# Low_Noise_PS_Bottom_SMD.net
KiCad netlist of a schematic drawn in EAGLE
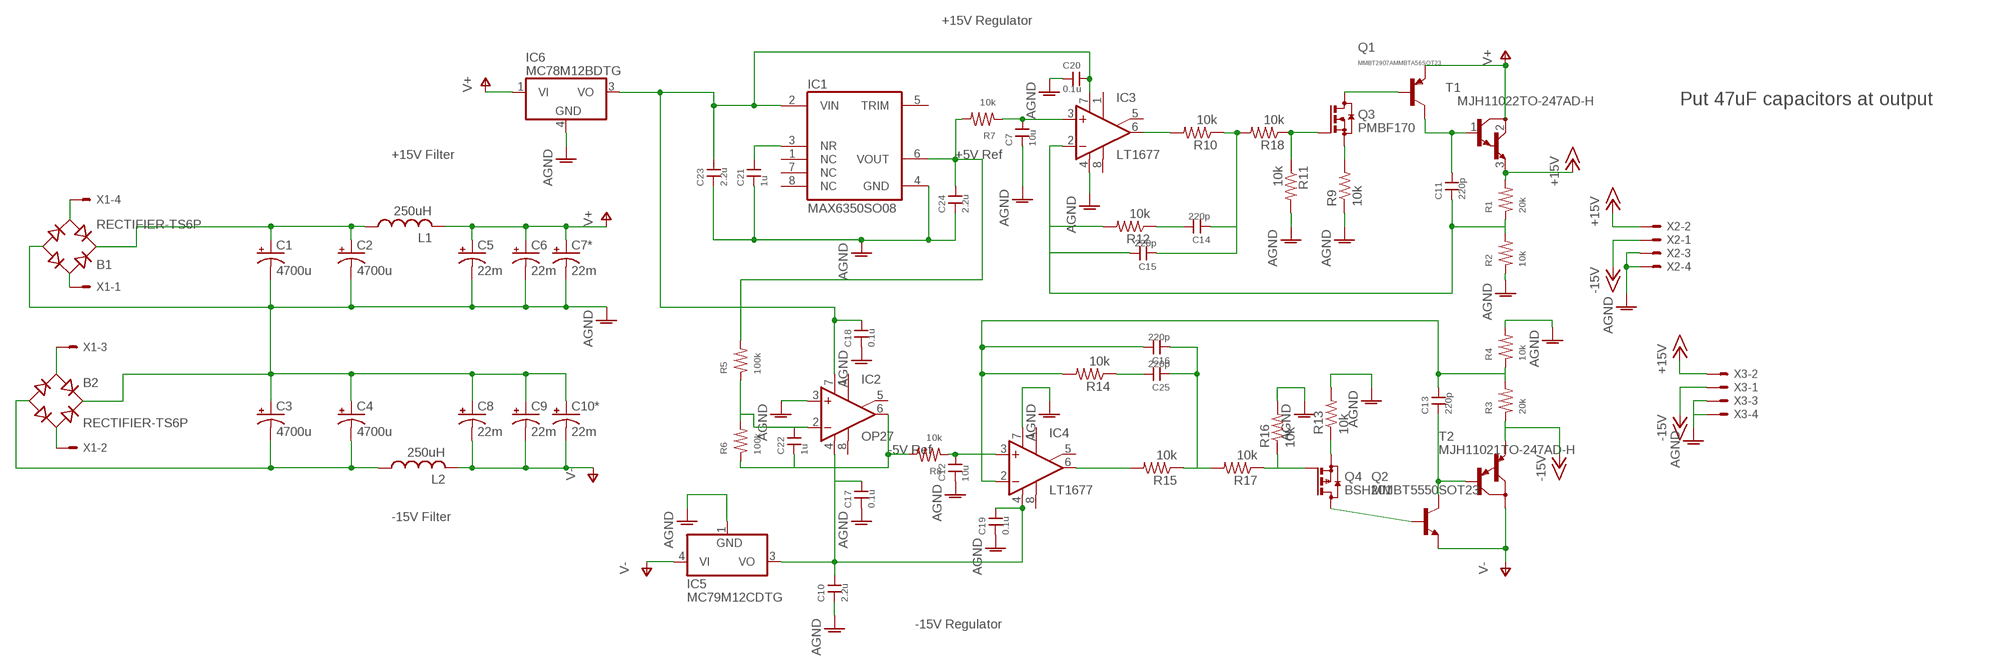
[diagram p0: schematic, sheet 1]

(export (version "E")
  (design (tool "Eeschema 10.0.6"))
  (components
    (comp (ref "B1")
      (value "RECTIFIER-TS6P")
      (footprint "eagle-import:TS6P")
      (libsource (lib "eagle-import") (part "RECTIFIER-TS6P"))
    )
    (comp (ref "B2")
      (value "RECTIFIER-TS6P")
      (footprint "eagle-import:TS6P")
      (libsource (lib "eagle-import") (part "RECTIFIER-TS6P"))
    )
    (comp (ref "C1")
      (value "4700u")
      (footprint "eagle-import:E7,5-18")
      (libsource (lib "eagle-import") (part "CPOL-USE7.5-18"))
    )
    (comp (ref "C2")
      (value "4700u")
      (footprint "eagle-import:E7,5-18")
      (libsource (lib "eagle-import") (part "CPOL-USE7.5-18"))
    )
    (comp (ref "C3")
      (value "4700u")
      (footprint "eagle-import:E7,5-18")
      (libsource (lib "eagle-import") (part "CPOL-USE7.5-18"))
    )
    (comp (ref "C4")
      (value "4700u")
      (footprint "eagle-import:E7,5-18")
      (libsource (lib "eagle-import") (part "CPOL-USE7.5-18"))
    )
    (comp (ref "C5")
      (value "22m")
      (footprint "eagle-import:EB35D")
      (libsource (lib "eagle-import") (part "CPOL-USEB35D"))
    )
    (comp (ref "C6")
      (value "22m")
      (footprint "eagle-import:EB35D")
      (libsource (lib "eagle-import") (part "CPOL-USEB35D"))
    )
    (comp (ref "C7")
      (value "10u")
      (footprint "eagle-import:1206")
      (libsource (lib "eagle-import") (part "CAP1206"))
    )
    (comp (ref "C7*")
      (value "22m")
      (footprint "eagle-import:EB35D")
      (libsource (lib "eagle-import") (part "CPOL-USEB35D"))
    )
    (comp (ref "C8")
      (value "22m")
      (footprint "eagle-import:EB35D")
      (libsource (lib "eagle-import") (part "CPOL-USEB35D"))
    )
    (comp (ref "C9")
      (value "22m")
      (footprint "eagle-import:EB35D")
      (libsource (lib "eagle-import") (part "CPOL-USEB35D"))
    )
    (comp (ref "C10")
      (value "2.2u")
      (footprint "eagle-import:1206")
      (libsource (lib "eagle-import") (part "CAP1206"))
    )
    (comp (ref "C10*")
      (value "22m")
      (footprint "eagle-import:EB35D")
      (libsource (lib "eagle-import") (part "CPOL-USEB35D"))
    )
    (comp (ref "C11")
      (value "220p")
      (footprint "eagle-import:1206")
      (libsource (lib "eagle-import") (part "CAP1206"))
    )
    (comp (ref "C12")
      (value "10u")
      (footprint "eagle-import:1206")
      (libsource (lib "eagle-import") (part "CAP1206"))
    )
    (comp (ref "C13")
      (value "220p")
      (footprint "eagle-import:1206")
      (libsource (lib "eagle-import") (part "CAP1206"))
    )
    (comp (ref "C14")
      (value "220p")
      (footprint "eagle-import:1206")
      (libsource (lib "eagle-import") (part "CAP1206"))
    )
    (comp (ref "C15")
      (value "220p")
      (footprint "eagle-import:1206")
      (libsource (lib "eagle-import") (part "CAP1206"))
    )
    (comp (ref "C16")
      (value "220p")
      (footprint "eagle-import:1206")
      (libsource (lib "eagle-import") (part "CAP1206"))
    )
    (comp (ref "C17")
      (value "0.1u")
      (footprint "eagle-import:1206")
      (libsource (lib "eagle-import") (part "CAP1206"))
    )
    (comp (ref "C18")
      (value "0.1u")
      (footprint "eagle-import:1206")
      (libsource (lib "eagle-import") (part "CAP1206"))
    )
    (comp (ref "C19")
      (value "0.1u")
      (footprint "eagle-import:1206")
      (libsource (lib "eagle-import") (part "CAP1206"))
    )
    (comp (ref "C20")
      (value "0.1u")
      (footprint "eagle-import:1206")
      (libsource (lib "eagle-import") (part "CAP1206"))
    )
    (comp (ref "C21")
      (value "1u")
      (footprint "eagle-import:1206")
      (libsource (lib "eagle-import") (part "CAP1206"))
    )
    (comp (ref "C22")
      (value "1u")
      (footprint "eagle-import:1206")
      (libsource (lib "eagle-import") (part "CAP1206"))
    )
    (comp (ref "C23")
      (value "2.2u")
      (footprint "eagle-import:1206")
      (libsource (lib "eagle-import") (part "CAP1206"))
    )
    (comp (ref "C24")
      (value "2.2u")
      (footprint "eagle-import:1206")
      (libsource (lib "eagle-import") (part "CAP1206"))
    )
    (comp (ref "C25")
      (value "220p")
      (footprint "eagle-import:1206")
      (libsource (lib "eagle-import") (part "CAP1206"))
    )
    (comp (ref "IC1")
      (value "MAX6350SO08")
      (footprint "eagle-import:SO08")
      (libsource (lib "eagle-import") (part "MAX6350SO08"))
    )
    (comp (ref "IC2")
      (value "OP27")
      (footprint "eagle-import:SO08")
      (libsource (lib "eagle-import") (part "OPAMP-SO"))
    )
    (comp (ref "IC3")
      (value "LT1677")
      (footprint "eagle-import:SO08")
      (libsource (lib "eagle-import") (part "OPAMP-SO"))
    )
    (comp (ref "IC4")
      (value "LT1677")
      (footprint "eagle-import:SO08")
      (libsource (lib "eagle-import") (part "OPAMP-SO"))
    )
    (comp (ref "IC5")
      (value "MC79M12CDTG")
      (footprint "eagle-import:DPACK_3")
      (libsource (lib "eagle-import") (part "MC79M12CDTG"))
    )
    (comp (ref "IC6")
      (value "MC78M12BDTG")
      (footprint "eagle-import:DPACK_3")
      (libsource (lib "eagle-import") (part "MC78M12BDTG"))
    )
    (comp (ref "L1")
      (value "250uH")
      (footprint "eagle-import:5721-RC")
      (libsource (lib "eagle-import") (part "INDUCTOR5721-RC"))
    )
    (comp (ref "L2")
      (value "250uH")
      (footprint "eagle-import:5721-RC")
      (libsource (lib "eagle-import") (part "INDUCTOR5721-RC"))
    )
    (comp (ref "Q1")
      (value "MMBT2907AMMBTA56SOT23")
      (footprint "eagle-import:SOT23")
      (libsource (lib "eagle-import") (part "MMBT2907ASOT23MMBTA56"))
    )
    (comp (ref "Q2")
      (value "MMBT5550SOT23")
      (footprint "eagle-import:SOT23")
      (libsource (lib "eagle-import") (part "MMBT5550SOT23"))
    )
    (comp (ref "Q3")
      (value "PMBF170")
      (footprint "eagle-import:SOT23")
      (libsource (lib "eagle-import") (part "PMBF170"))
    )
    (comp (ref "Q4")
      (value "BSH201")
      (footprint "eagle-import:SOT23")
      (libsource (lib "eagle-import") (part "BSH201"))
    )
    (comp (ref "R1")
      (value "20k")
      (footprint "eagle-import:1206")
      (libsource (lib "eagle-import") (part "RES1206"))
    )
    (comp (ref "R2")
      (value "10k")
      (footprint "eagle-import:1206")
      (libsource (lib "eagle-import") (part "RES1206"))
    )
    (comp (ref "R3")
      (value "20k")
      (footprint "eagle-import:1206")
      (libsource (lib "eagle-import") (part "RES1206"))
    )
    (comp (ref "R4")
      (value "10k")
      (footprint "eagle-import:1206")
      (libsource (lib "eagle-import") (part "RES1206"))
    )
    (comp (ref "R5")
      (value "100k")
      (footprint "eagle-import:1206")
      (libsource (lib "eagle-import") (part "RES1206"))
    )
    (comp (ref "R6")
      (value "100k")
      (footprint "eagle-import:1206")
      (libsource (lib "eagle-import") (part "RES1206"))
    )
    (comp (ref "R7")
      (value "10k")
      (footprint "eagle-import:1206")
      (libsource (lib "eagle-import") (part "RES1206"))
    )
    (comp (ref "R8")
      (value "10k")
      (footprint "eagle-import:1206")
      (libsource (lib "eagle-import") (part "RES1206"))
    )
    (comp (ref "R9")
      (value "10k")
      (footprint "eagle-import:R1206")
      (libsource (lib "eagle-import") (part "R-US_R1206"))
    )
    (comp (ref "R10")
      (value "10k")
      (footprint "eagle-import:R1206")
      (libsource (lib "eagle-import") (part "R-US_R1206"))
    )
    (comp (ref "R11")
      (value "10k")
      (footprint "eagle-import:R1206")
      (libsource (lib "eagle-import") (part "R-US_R1206"))
    )
    (comp (ref "R12")
      (value "10k")
      (footprint "eagle-import:R1206")
      (libsource (lib "eagle-import") (part "R-US_R1206"))
    )
    (comp (ref "R13")
      (value "10k")
      (footprint "eagle-import:R1206")
      (libsource (lib "eagle-import") (part "R-US_R1206"))
    )
    (comp (ref "R14")
      (value "10k")
      (footprint "eagle-import:R1206")
      (libsource (lib "eagle-import") (part "R-US_R1206"))
    )
    (comp (ref "R15")
      (value "10k")
      (footprint "eagle-import:R1206")
      (libsource (lib "eagle-import") (part "R-US_R1206"))
    )
    (comp (ref "R16")
      (value "10k")
      (footprint "eagle-import:R1206")
      (libsource (lib "eagle-import") (part "R-US_R1206"))
    )
    (comp (ref "R17")
      (value "10k")
      (footprint "eagle-import:R1206")
      (libsource (lib "eagle-import") (part "R-US_R1206"))
    )
    (comp (ref "R18")
      (value "10k")
      (footprint "eagle-import:R1206")
      (libsource (lib "eagle-import") (part "R-US_R1206"))
    )
    (comp (ref "T1")
      (value "MJH11022TO-247AD-H")
      (footprint "eagle-import:TO-247AD-H")
      (libsource (lib "eagle-import") (part "MJH11022TO-247AD-H"))
    )
    (comp (ref "T2")
      (value "MJH11021TO-247AD-H")
      (footprint "eagle-import:TO-247AD-H")
      (libsource (lib "eagle-import") (part "MJH11021TO-247AD-H"))
    )
    (comp (ref "X1")
      (value "5566-4RA")
      (footprint "eagle-import:5566-4-RA")
      (libsource (lib "eagle-import") (part "5566-4RA"))
    )
    (comp (ref "X2")
      (value "5566-4RA")
      (footprint "eagle-import:5566-4-RA")
      (libsource (lib "eagle-import") (part "5566-4RA"))
    )
    (comp (ref "X3")
      (value "5566-4RA")
      (footprint "eagle-import:5566-4-RA")
      (libsource (lib "eagle-import") (part "5566-4RA"))
    )
  )
  (nets
    (net (code "1") (name "+15V") (class "Default")
      (node (ref "R1") (pin "2") (pinfunction "P$2_2") (pintype "passive"))
      (node (ref "T1") (pin "3") (pinfunction "E_3") (pintype "passive"))
      (node (ref "X2") (pin "2") (pinfunction "S_2") (pintype "passive"))
      (node (ref "X3") (pin "2") (pinfunction "S_2") (pintype "passive"))
    )
    (net (code "2") (name "-15V") (class "Default")
      (node (ref "R3") (pin "1") (pinfunction "P$1_1") (pintype "passive"))
      (node (ref "T2") (pin "3") (pinfunction "E_3") (pintype "passive"))
      (node (ref "X2") (pin "1") (pinfunction "S_1") (pintype "passive"))
      (node (ref "X3") (pin "1") (pinfunction "S_1") (pintype "passive"))
    )
    (net (code "3") (name "AGND") (class "Default")
      (node (ref "B1") (pin "-") (pinfunction "-_-") (pintype "passive"))
      (node (ref "B2") (pin "+") (pinfunction "+_+") (pintype "passive"))
      (node (ref "C1") (pin "-") (pinfunction "-_-") (pintype "passive"))
      (node (ref "C10") (pin "1") (pinfunction "P$1_1") (pintype "passive"))
      (node (ref "C10*") (pin "+") (pinfunction "+_+") (pintype "passive"))
      (node (ref "C12") (pin "1") (pinfunction "P$1_1") (pintype "passive"))
      (node (ref "C17") (pin "1") (pinfunction "P$1_1") (pintype "passive"))
      (node (ref "C18") (pin "1") (pinfunction "P$1_1") (pintype "passive"))
      (node (ref "C19") (pin "1") (pinfunction "P$1_1") (pintype "passive"))
      (node (ref "C2") (pin "-") (pinfunction "-_-") (pintype "passive"))
      (node (ref "C20") (pin "1") (pinfunction "P$1_1") (pintype "passive"))
      (node (ref "C21") (pin "1") (pinfunction "P$1_1") (pintype "passive"))
      (node (ref "C23") (pin "1") (pinfunction "P$1_1") (pintype "passive"))
      (node (ref "C24") (pin "1") (pinfunction "P$1_1") (pintype "passive"))
      (node (ref "C3") (pin "+") (pinfunction "+_+") (pintype "passive"))
      (node (ref "C4") (pin "+") (pinfunction "+_+") (pintype "passive"))
      (node (ref "C5") (pin "-") (pinfunction "-_-") (pintype "passive"))
      (node (ref "C6") (pin "-") (pinfunction "-_-") (pintype "passive"))
      (node (ref "C7") (pin "1") (pinfunction "P$1_1") (pintype "passive"))
      (node (ref "C7*") (pin "-") (pinfunction "-_-") (pintype "passive"))
      (node (ref "C8") (pin "+") (pinfunction "+_+") (pintype "passive"))
      (node (ref "C9") (pin "+") (pinfunction "+_+") (pintype "passive"))
      (node (ref "IC1") (pin "4") (pinfunction "GND_4") (pintype "power_in"))
      (node (ref "IC2") (pin "3") (pinfunction "+IN_3") (pintype "input"))
      (node (ref "IC3") (pin "4") (pinfunction "V-_4") (pintype "power_in"))
      (node (ref "IC4") (pin "7") (pinfunction "V+_7") (pintype "power_in"))
      (node (ref "IC5") (pin "1") (pinfunction "GND_1") (pintype "passive"))
      (node (ref "IC6") (pin "4") (pinfunction "GND_4") (pintype "passive"))
      (node (ref "R11") (pin "2") (pinfunction "2_2") (pintype "passive"))
      (node (ref "R13") (pin "2") (pinfunction "2_2") (pintype "passive"))
      (node (ref "R16") (pin "2") (pinfunction "2_2") (pintype "passive"))
      (node (ref "R2") (pin "1") (pinfunction "P$1_1") (pintype "passive"))
      (node (ref "R4") (pin "2") (pinfunction "P$2_2") (pintype "passive"))
      (node (ref "R9") (pin "1") (pinfunction "1_1") (pintype "passive"))
      (node (ref "X2") (pin "3") (pinfunction "S_3") (pintype "passive"))
      (node (ref "X2") (pin "4") (pinfunction "S_4") (pintype "passive"))
      (node (ref "X3") (pin "3") (pinfunction "S_3") (pintype "passive"))
      (node (ref "X3") (pin "4") (pinfunction "S_4") (pintype "passive"))
    )
    (net (code "4") (name "Net-(C7-P$2)") (class "Default")
      (node (ref "C7") (pin "2") (pinfunction "P$2_2") (pintype "passive"))
      (node (ref "IC3") (pin "3") (pinfunction "+IN_3") (pintype "input"))
      (node (ref "R7") (pin "1") (pinfunction "P$1_1") (pintype "passive"))
    )
    (net (code "5") (name "Net-(C10-P$2)") (class "Default")
      (node (ref "C10") (pin "2") (pinfunction "P$2_2") (pintype "passive"))
      (node (ref "C17") (pin "2") (pinfunction "P$2_2") (pintype "passive"))
      (node (ref "C19") (pin "2") (pinfunction "P$2_2") (pintype "passive"))
      (node (ref "IC2") (pin "4") (pinfunction "V-_4") (pintype "power_in"))
      (node (ref "IC4") (pin "4") (pinfunction "V-_4") (pintype "power_in"))
      (node (ref "IC5") (pin "3") (pinfunction "VO_3") (pintype "passive"))
    )
    (net (code "6") (name "Net-(C11-P$1)") (class "Default")
      (node (ref "C11") (pin "1") (pinfunction "P$1_1") (pintype "passive"))
      (node (ref "C15") (pin "2") (pinfunction "P$2_2") (pintype "passive"))
      (node (ref "IC3") (pin "2") (pinfunction "-IN_2") (pintype "input"))
      (node (ref "R1") (pin "1") (pinfunction "P$1_1") (pintype "passive"))
      (node (ref "R12") (pin "2") (pinfunction "2_2") (pintype "passive"))
      (node (ref "R2") (pin "2") (pinfunction "P$2_2") (pintype "passive"))
    )
    (net (code "7") (name "Net-(C11-P$2)") (class "Default")
      (node (ref "C11") (pin "2") (pinfunction "P$2_2") (pintype "passive"))
      (node (ref "Q1") (pin "3") (pinfunction "C_3") (pintype "passive"))
      (node (ref "T1") (pin "1") (pinfunction "B_1") (pintype "passive"))
    )
    (net (code "8") (name "Net-(C12-P$2)") (class "Default")
      (node (ref "C12") (pin "2") (pinfunction "P$2_2") (pintype "passive"))
      (node (ref "IC4") (pin "3") (pinfunction "+IN_3") (pintype "input"))
      (node (ref "R8") (pin "1") (pinfunction "P$1_1") (pintype "passive"))
    )
    (net (code "9") (name "Net-(C13-P$1)") (class "Default")
      (node (ref "C13") (pin "1") (pinfunction "P$1_1") (pintype "passive"))
      (node (ref "Q2") (pin "3") (pinfunction "C_3") (pintype "passive"))
      (node (ref "T2") (pin "1") (pinfunction "B_1") (pintype "passive"))
    )
    (net (code "10") (name "Net-(C13-P$2)") (class "Default")
      (node (ref "C13") (pin "2") (pinfunction "P$2_2") (pintype "passive"))
      (node (ref "C16") (pin "2") (pinfunction "P$2_2") (pintype "passive"))
      (node (ref "IC4") (pin "2") (pinfunction "-IN_2") (pintype "input"))
      (node (ref "R14") (pin "2") (pinfunction "2_2") (pintype "passive"))
      (node (ref "R3") (pin "2") (pinfunction "P$2_2") (pintype "passive"))
      (node (ref "R4") (pin "1") (pinfunction "P$1_1") (pintype "passive"))
    )
    (net (code "11") (name "Net-(C14-P$1)") (class "Default")
      (node (ref "C14") (pin "1") (pinfunction "P$1_1") (pintype "passive"))
      (node (ref "C15") (pin "1") (pinfunction "P$1_1") (pintype "passive"))
      (node (ref "R10") (pin "1") (pinfunction "1_1") (pintype "passive"))
      (node (ref "R18") (pin "2") (pinfunction "2_2") (pintype "passive"))
    )
    (net (code "12") (name "Net-(C14-P$2)") (class "Default")
      (node (ref "C14") (pin "2") (pinfunction "P$2_2") (pintype "passive"))
      (node (ref "R12") (pin "1") (pinfunction "1_1") (pintype "passive"))
    )
    (net (code "13") (name "Net-(C16-P$1)") (class "Default")
      (node (ref "C16") (pin "1") (pinfunction "P$1_1") (pintype "passive"))
      (node (ref "C25") (pin "1") (pinfunction "P$1_1") (pintype "passive"))
      (node (ref "R15") (pin "1") (pinfunction "1_1") (pintype "passive"))
      (node (ref "R17") (pin "2") (pinfunction "2_2") (pintype "passive"))
    )
    (net (code "14") (name "Net-(C18-P$2)") (class "Default")
      (node (ref "C18") (pin "2") (pinfunction "P$2_2") (pintype "passive"))
      (node (ref "C20") (pin "2") (pinfunction "P$2_2") (pintype "passive"))
      (node (ref "C23") (pin "2") (pinfunction "P$2_2") (pintype "passive"))
      (node (ref "IC1") (pin "2") (pinfunction "VIN_2") (pintype "input"))
      (node (ref "IC2") (pin "7") (pinfunction "V+_7") (pintype "power_in"))
      (node (ref "IC3") (pin "7") (pinfunction "V+_7") (pintype "power_in"))
      (node (ref "IC6") (pin "3") (pinfunction "VO_3") (pintype "passive"))
    )
    (net (code "15") (name "Net-(C21-P$2)") (class "Default")
      (node (ref "C21") (pin "2") (pinfunction "P$2_2") (pintype "passive"))
      (node (ref "IC1") (pin "3") (pinfunction "NR_3") (pintype "bidirectional"))
    )
    (net (code "16") (name "Net-(C22-P$1)") (class "Default")
      (node (ref "C22") (pin "1") (pinfunction "P$1_1") (pintype "passive"))
      (node (ref "IC2") (pin "6") (pinfunction "OUT_6") (pintype "output"))
      (node (ref "R6") (pin "1") (pinfunction "P$1_1") (pintype "passive"))
      (node (ref "R8") (pin "2") (pinfunction "P$2_2") (pintype "passive"))
    )
    (net (code "17") (name "Net-(C22-P$2)") (class "Default")
      (node (ref "C22") (pin "2") (pinfunction "P$2_2") (pintype "passive"))
      (node (ref "IC2") (pin "2") (pinfunction "-IN_2") (pintype "input"))
      (node (ref "R5") (pin "1") (pinfunction "P$1_1") (pintype "passive"))
      (node (ref "R6") (pin "2") (pinfunction "P$2_2") (pintype "passive"))
    )
    (net (code "18") (name "Net-(C24-P$2)") (class "Default")
      (node (ref "C24") (pin "2") (pinfunction "P$2_2") (pintype "passive"))
      (node (ref "IC1") (pin "6") (pinfunction "VOUT_6") (pintype "power_in"))
      (node (ref "R5") (pin "2") (pinfunction "P$2_2") (pintype "passive"))
      (node (ref "R7") (pin "2") (pinfunction "P$2_2") (pintype "passive"))
    )
    (net (code "19") (name "Net-(C25-P$2)") (class "Default")
      (node (ref "C25") (pin "2") (pinfunction "P$2_2") (pintype "passive"))
      (node (ref "R14") (pin "1") (pinfunction "1_1") (pintype "passive"))
    )
    (net (code "20") (name "Net-(IC3-OUT)") (class "Default")
      (node (ref "IC3") (pin "6") (pinfunction "OUT_6") (pintype "output"))
      (node (ref "R10") (pin "2") (pinfunction "2_2") (pintype "passive"))
    )
    (net (code "21") (name "Net-(IC4-OUT)") (class "Default")
      (node (ref "IC4") (pin "6") (pinfunction "OUT_6") (pintype "output"))
      (node (ref "R15") (pin "2") (pinfunction "2_2") (pintype "passive"))
    )
    (net (code "22") (name "Net-(L1-1)") (class "Default")
      (node (ref "B1") (pin "+") (pinfunction "+_+") (pintype "passive"))
      (node (ref "C1") (pin "+") (pinfunction "+_+") (pintype "passive"))
      (node (ref "C2") (pin "+") (pinfunction "+_+") (pintype "passive"))
      (node (ref "L1") (pin "P$1") (pinfunction "1_P$1") (pintype "passive"))
    )
    (net (code "23") (name "Net-(L2-1)") (class "Default")
      (node (ref "B2") (pin "-") (pinfunction "-_-") (pintype "passive"))
      (node (ref "C3") (pin "-") (pinfunction "-_-") (pintype "passive"))
      (node (ref "C4") (pin "-") (pinfunction "-_-") (pintype "passive"))
      (node (ref "L2") (pin "P$1") (pinfunction "1_P$1") (pintype "passive"))
    )
    (net (code "24") (name "Net-(Q1-B)") (class "Default")
      (node (ref "Q1") (pin "1") (pinfunction "B_1") (pintype "passive"))
      (node (ref "Q3") (pin "3") (pinfunction "D_3") (pintype "passive"))
    )
    (net (code "25") (name "Net-(Q2-B)") (class "Default")
      (node (ref "Q2") (pin "1") (pinfunction "B_1") (pintype "passive"))
      (node (ref "Q4") (pin "3") (pinfunction "D_3") (pintype "passive"))
    )
    (net (code "26") (name "Net-(Q3-G)") (class "Default")
      (node (ref "Q3") (pin "1") (pinfunction "G_1") (pintype "passive"))
      (node (ref "R11") (pin "1") (pinfunction "1_1") (pintype "passive"))
      (node (ref "R18") (pin "1") (pinfunction "1_1") (pintype "passive"))
    )
    (net (code "27") (name "Net-(Q3-S)") (class "Default")
      (node (ref "Q3") (pin "2") (pinfunction "S_2") (pintype "passive"))
      (node (ref "R9") (pin "2") (pinfunction "2_2") (pintype "passive"))
    )
    (net (code "28") (name "Net-(Q4-G)") (class "Default")
      (node (ref "Q4") (pin "1") (pinfunction "G_1") (pintype "passive"))
      (node (ref "R16") (pin "1") (pinfunction "1_1") (pintype "passive"))
      (node (ref "R17") (pin "1") (pinfunction "1_1") (pintype "passive"))
    )
    (net (code "29") (name "Net-(Q4-S)") (class "Default")
      (node (ref "Q4") (pin "2") (pinfunction "S_2") (pintype "passive"))
      (node (ref "R13") (pin "1") (pinfunction "1_1") (pintype "passive"))
    )
    (net (code "30") (name "Net-(X1A-S)") (class "Default")
      (node (ref "B1") (pin "AC1") (pinfunction "AC1_AC1") (pintype "passive"))
      (node (ref "X1") (pin "1") (pinfunction "S_1") (pintype "passive"))
    )
    (net (code "31") (name "Net-(X1B-S)") (class "Default")
      (node (ref "B2") (pin "AC2") (pinfunction "AC2_AC2") (pintype "passive"))
      (node (ref "X1") (pin "2") (pinfunction "S_2") (pintype "passive"))
    )
    (net (code "32") (name "Net-(X1C-S)") (class "Default")
      (node (ref "B2") (pin "AC1") (pinfunction "AC1_AC1") (pintype "passive"))
      (node (ref "X1") (pin "3") (pinfunction "S_3") (pintype "passive"))
    )
    (net (code "33") (name "Net-(X1D-S)") (class "Default")
      (node (ref "B1") (pin "AC2") (pinfunction "AC2_AC2") (pintype "passive"))
      (node (ref "X1") (pin "4") (pinfunction "S_4") (pintype "passive"))
    )
    (net (code "34") (name "V+") (class "Default")
      (node (ref "C5") (pin "+") (pinfunction "+_+") (pintype "passive"))
      (node (ref "C6") (pin "+") (pinfunction "+_+") (pintype "passive"))
      (node (ref "C7*") (pin "+") (pinfunction "+_+") (pintype "passive"))
      (node (ref "IC6") (pin "1") (pinfunction "VI_1") (pintype "input"))
      (node (ref "L1") (pin "P$2") (pinfunction "2_P$2") (pintype "passive"))
      (node (ref "Q1") (pin "2") (pinfunction "E_2") (pintype "passive"))
      (node (ref "T1") (pin "2") (pinfunction "C_2") (pintype "passive"))
    )
    (net (code "35") (name "V-") (class "Default")
      (node (ref "C10*") (pin "-") (pinfunction "-_-") (pintype "passive"))
      (node (ref "C8") (pin "-") (pinfunction "-_-") (pintype "passive"))
      (node (ref "C9") (pin "-") (pinfunction "-_-") (pintype "passive"))
      (node (ref "IC5") (pin "4") (pinfunction "VI_4") (pintype "input"))
      (node (ref "L2") (pin "P$2") (pinfunction "2_P$2") (pintype "passive"))
      (node (ref "Q2") (pin "2") (pinfunction "E_2") (pintype "passive"))
      (node (ref "T2") (pin "2") (pinfunction "C_2") (pintype "passive"))
    )
    (net (code "36") (name "unconnected-(IC1-NC-Pad1)") (class "Default")
      (node (ref "IC1") (pin "1") (pinfunction "NC_1") (pintype "no_connect"))
    )
    (net (code "37") (name "unconnected-(IC1-NC-Pad7)") (class "Default")
      (node (ref "IC1") (pin "7") (pinfunction "NC_7") (pintype "no_connect"))
    )
    (net (code "38") (name "unconnected-(IC1-NC-Pad8)") (class "Default")
      (node (ref "IC1") (pin "8") (pinfunction "NC_8") (pintype "no_connect"))
    )
    (net (code "39") (name "unconnected-(IC1-TRIM-Pad5)") (class "Default")
      (node (ref "IC1") (pin "5") (pinfunction "TRIM_5") (pintype "input"))
    )
    (net (code "40") (name "unconnected-(IC2-ON1-Pad1)") (class "Default")
      (node (ref "IC2") (pin "1") (pinfunction "ON1_1") (pintype "passive"))
    )
    (net (code "41") (name "unconnected-(IC2-ON2-Pad5)") (class "Default")
      (node (ref "IC2") (pin "5") (pinfunction "ON2_5") (pintype "passive"))
    )
    (net (code "42") (name "unconnected-(IC2-OPT-Pad8)") (class "Default")
      (node (ref "IC2") (pin "8") (pinfunction "OPT_8") (pintype "passive"))
    )
    (net (code "43") (name "unconnected-(IC3-ON1-Pad1)") (class "Default")
      (node (ref "IC3") (pin "1") (pinfunction "ON1_1") (pintype "passive"))
    )
    (net (code "44") (name "unconnected-(IC3-ON2-Pad5)") (class "Default")
      (node (ref "IC3") (pin "5") (pinfunction "ON2_5") (pintype "passive"))
    )
    (net (code "45") (name "unconnected-(IC3-OPT-Pad8)") (class "Default")
      (node (ref "IC3") (pin "8") (pinfunction "OPT_8") (pintype "passive"))
    )
    (net (code "46") (name "unconnected-(IC4-ON1-Pad1)") (class "Default")
      (node (ref "IC4") (pin "1") (pinfunction "ON1_1") (pintype "passive"))
    )
    (net (code "47") (name "unconnected-(IC4-ON2-Pad5)") (class "Default")
      (node (ref "IC4") (pin "5") (pinfunction "ON2_5") (pintype "passive"))
    )
    (net (code "48") (name "unconnected-(IC4-OPT-Pad8)") (class "Default")
      (node (ref "IC4") (pin "8") (pinfunction "OPT_8") (pintype "passive"))
    )
  )
)
